# right-angle-extender.net
KiCad netlist of a schematic drawn in EAGLE
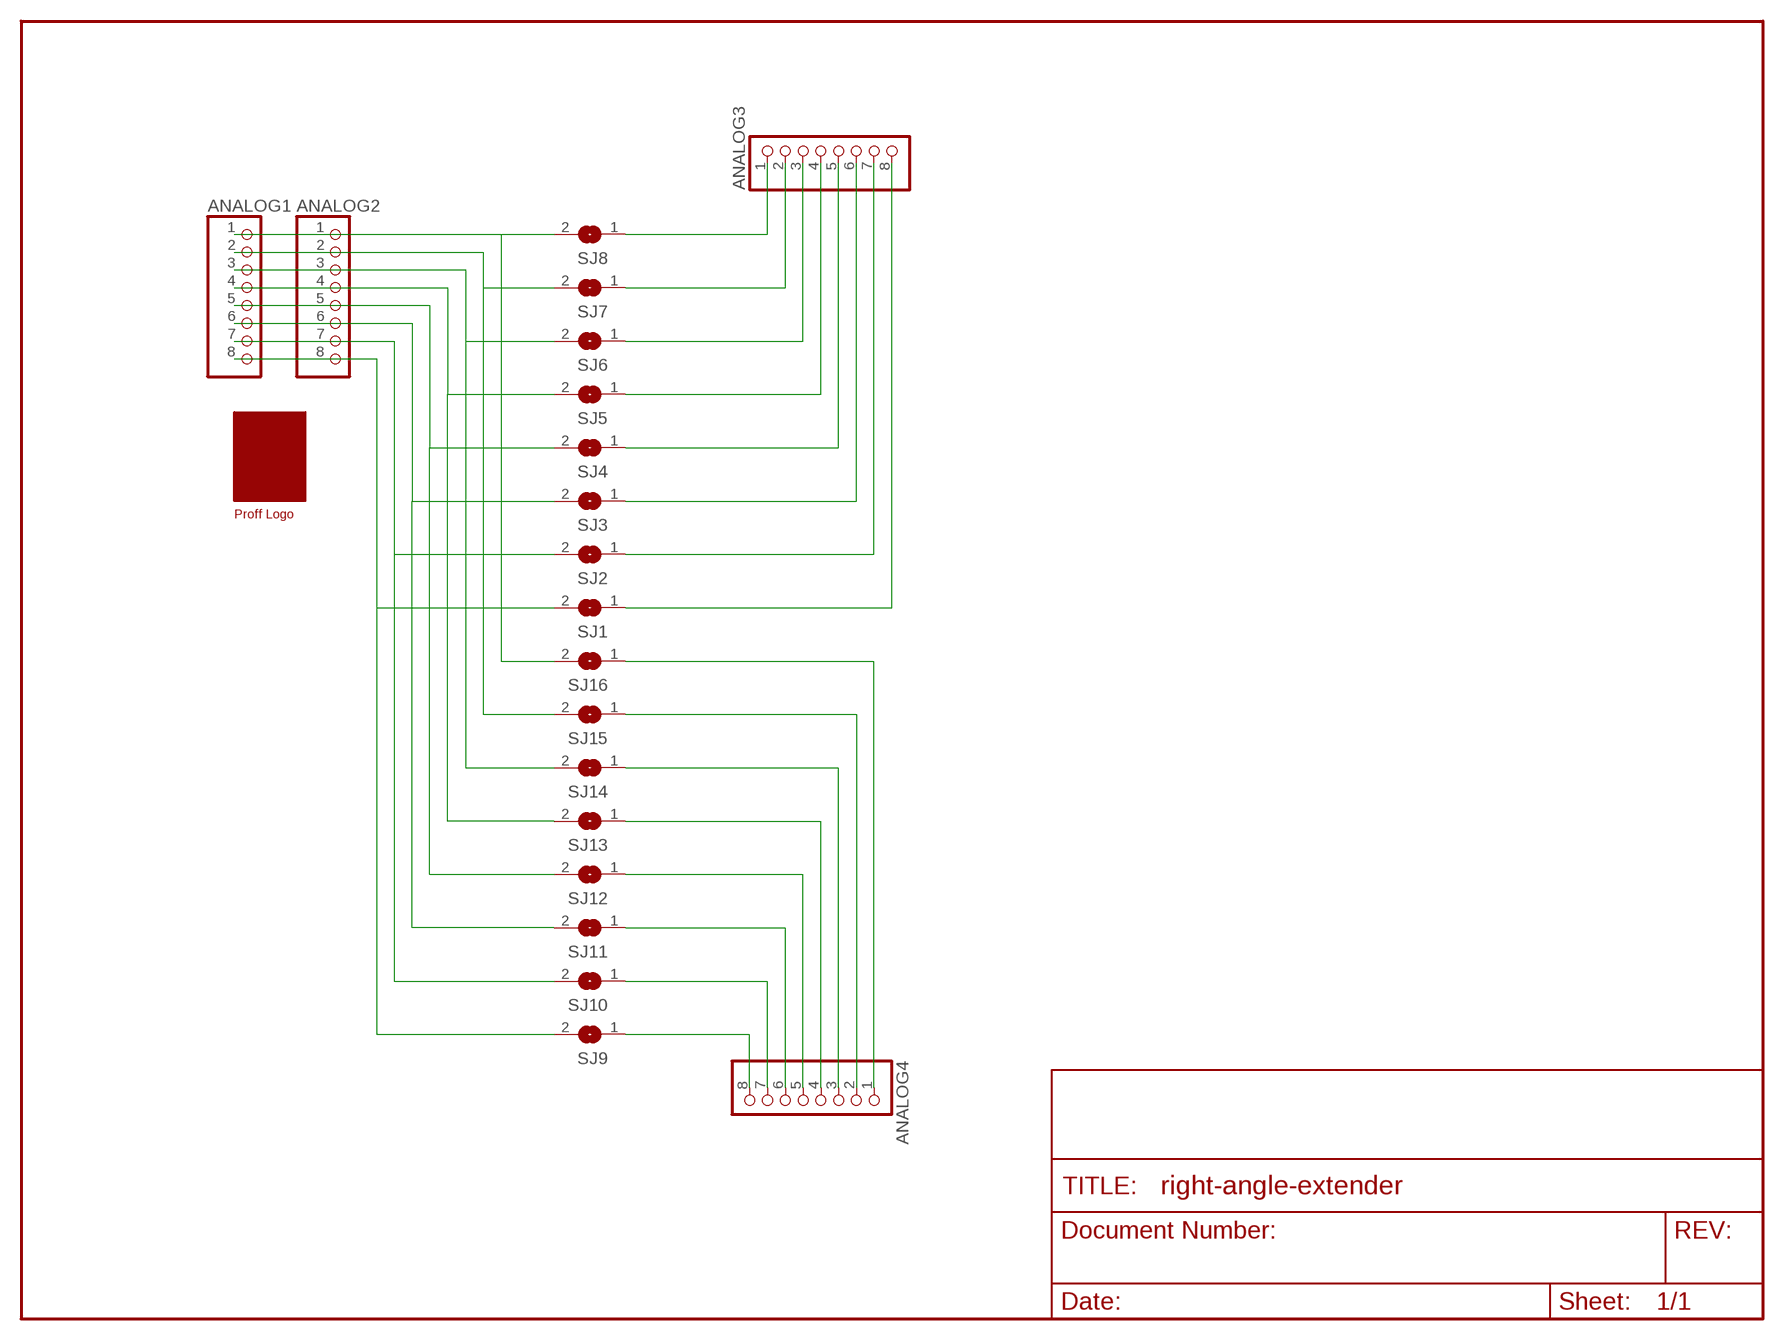
[diagram p0: schematic, sheet 1]

(export (version "E")
  (design (tool "Eeschema 10.0.6"))
  (components
    (comp (ref "ANALOG1")
      (value "PINHD-1X8")
      (footprint "eagle-import:1X08")
      (libsource (lib "eagle-import") (part "PINHD-1X8"))
    )
    (comp (ref "ANALOG2")
      (value "PINHD-1X8")
      (footprint "eagle-import:1X08")
      (libsource (lib "eagle-import") (part "PINHD-1X8"))
    )
    (comp (ref "ANALOG3")
      (value "PINHD-1X8")
      (footprint "eagle-import:1X08")
      (libsource (lib "eagle-import") (part "PINHD-1X8"))
    )
    (comp (ref "ANALOG4")
      (value "PINHD-1X8")
      (footprint "eagle-import:1X08")
      (libsource (lib "eagle-import") (part "PINHD-1X8"))
    )
    (comp (ref "SJ1") (value "SJ") (footprint "eagle-import:SJ") (libsource (lib "eagle-import") (part "SJ")))
    (comp (ref "SJ2") (value "SJ") (footprint "eagle-import:SJ") (libsource (lib "eagle-import") (part "SJ")))
    (comp (ref "SJ3") (value "SJ") (footprint "eagle-import:SJ") (libsource (lib "eagle-import") (part "SJ")))
    (comp (ref "SJ4") (value "SJ") (footprint "eagle-import:SJ") (libsource (lib "eagle-import") (part "SJ")))
    (comp (ref "SJ5") (value "SJ") (footprint "eagle-import:SJ") (libsource (lib "eagle-import") (part "SJ")))
    (comp (ref "SJ6") (value "SJ") (footprint "eagle-import:SJ") (libsource (lib "eagle-import") (part "SJ")))
    (comp (ref "SJ7") (value "SJ") (footprint "eagle-import:SJ") (libsource (lib "eagle-import") (part "SJ")))
    (comp (ref "SJ8") (value "SJ") (footprint "eagle-import:SJ") (libsource (lib "eagle-import") (part "SJ")))
    (comp (ref "SJ9") (value "SJ") (footprint "eagle-import:SJ") (libsource (lib "eagle-import") (part "SJ")))
    (comp (ref "SJ10")
      (value "SJ")
      (footprint "eagle-import:SJ")
      (libsource (lib "eagle-import") (part "SJ"))
    )
    (comp (ref "SJ11")
      (value "SJ")
      (footprint "eagle-import:SJ")
      (libsource (lib "eagle-import") (part "SJ"))
    )
    (comp (ref "SJ12")
      (value "SJ")
      (footprint "eagle-import:SJ")
      (libsource (lib "eagle-import") (part "SJ"))
    )
    (comp (ref "SJ13")
      (value "SJ")
      (footprint "eagle-import:SJ")
      (libsource (lib "eagle-import") (part "SJ"))
    )
    (comp (ref "SJ14")
      (value "SJ")
      (footprint "eagle-import:SJ")
      (libsource (lib "eagle-import") (part "SJ"))
    )
    (comp (ref "SJ15")
      (value "SJ")
      (footprint "eagle-import:SJ")
      (libsource (lib "eagle-import") (part "SJ"))
    )
    (comp (ref "SJ16")
      (value "SJ")
      (footprint "eagle-import:SJ")
      (libsource (lib "eagle-import") (part "SJ"))
    )
    (comp (ref "U$1")
      (value "PROFF")
      (footprint "eagle-import:PROFF")
      (libsource (lib "eagle-import") (part "PROFF"))
    )
  )
  (nets
    (net (code "1") (name "Net-(ANALOG1-Pad1)") (class "Default")
      (node (ref "ANALOG1") (pin "1") (pinfunction "1_1") (pintype "passive"))
      (node (ref "ANALOG2") (pin "1") (pinfunction "1_1") (pintype "passive"))
      (node (ref "SJ16") (pin "2") (pinfunction "2_2") (pintype "passive"))
      (node (ref "SJ8") (pin "2") (pinfunction "2_2") (pintype "passive"))
    )
    (net (code "2") (name "Net-(ANALOG1-Pad2)") (class "Default")
      (node (ref "ANALOG1") (pin "2") (pinfunction "2_2") (pintype "passive"))
      (node (ref "ANALOG2") (pin "2") (pinfunction "2_2") (pintype "passive"))
      (node (ref "SJ15") (pin "2") (pinfunction "2_2") (pintype "passive"))
      (node (ref "SJ7") (pin "2") (pinfunction "2_2") (pintype "passive"))
    )
    (net (code "3") (name "Net-(ANALOG1-Pad3)") (class "Default")
      (node (ref "ANALOG1") (pin "3") (pinfunction "3_3") (pintype "passive"))
      (node (ref "ANALOG2") (pin "3") (pinfunction "3_3") (pintype "passive"))
      (node (ref "SJ14") (pin "2") (pinfunction "2_2") (pintype "passive"))
      (node (ref "SJ6") (pin "2") (pinfunction "2_2") (pintype "passive"))
    )
    (net (code "4") (name "Net-(ANALOG1-Pad4)") (class "Default")
      (node (ref "ANALOG1") (pin "4") (pinfunction "4_4") (pintype "passive"))
      (node (ref "ANALOG2") (pin "4") (pinfunction "4_4") (pintype "passive"))
      (node (ref "SJ13") (pin "2") (pinfunction "2_2") (pintype "passive"))
      (node (ref "SJ5") (pin "2") (pinfunction "2_2") (pintype "passive"))
    )
    (net (code "5") (name "Net-(ANALOG1-Pad5)") (class "Default")
      (node (ref "ANALOG1") (pin "5") (pinfunction "5_5") (pintype "passive"))
      (node (ref "ANALOG2") (pin "5") (pinfunction "5_5") (pintype "passive"))
      (node (ref "SJ12") (pin "2") (pinfunction "2_2") (pintype "passive"))
      (node (ref "SJ4") (pin "2") (pinfunction "2_2") (pintype "passive"))
    )
    (net (code "6") (name "Net-(ANALOG1-Pad6)") (class "Default")
      (node (ref "ANALOG1") (pin "6") (pinfunction "6_6") (pintype "passive"))
      (node (ref "ANALOG2") (pin "6") (pinfunction "6_6") (pintype "passive"))
      (node (ref "SJ11") (pin "2") (pinfunction "2_2") (pintype "passive"))
      (node (ref "SJ3") (pin "2") (pinfunction "2_2") (pintype "passive"))
    )
    (net (code "7") (name "Net-(ANALOG1-Pad7)") (class "Default")
      (node (ref "ANALOG1") (pin "7") (pinfunction "7_7") (pintype "passive"))
      (node (ref "ANALOG2") (pin "7") (pinfunction "7_7") (pintype "passive"))
      (node (ref "SJ10") (pin "2") (pinfunction "2_2") (pintype "passive"))
      (node (ref "SJ2") (pin "2") (pinfunction "2_2") (pintype "passive"))
    )
    (net (code "8") (name "Net-(ANALOG1-Pad8)") (class "Default")
      (node (ref "ANALOG1") (pin "8") (pinfunction "8_8") (pintype "passive"))
      (node (ref "ANALOG2") (pin "8") (pinfunction "8_8") (pintype "passive"))
      (node (ref "SJ1") (pin "2") (pinfunction "2_2") (pintype "passive"))
      (node (ref "SJ9") (pin "2") (pinfunction "2_2") (pintype "passive"))
    )
    (net (code "9") (name "Net-(ANALOG3-Pad1)") (class "Default")
      (node (ref "ANALOG3") (pin "1") (pinfunction "1_1") (pintype "passive"))
      (node (ref "SJ8") (pin "1") (pinfunction "1_1") (pintype "passive"))
    )
    (net (code "10") (name "Net-(ANALOG3-Pad2)") (class "Default")
      (node (ref "ANALOG3") (pin "2") (pinfunction "2_2") (pintype "passive"))
      (node (ref "SJ7") (pin "1") (pinfunction "1_1") (pintype "passive"))
    )
    (net (code "11") (name "Net-(ANALOG3-Pad3)") (class "Default")
      (node (ref "ANALOG3") (pin "3") (pinfunction "3_3") (pintype "passive"))
      (node (ref "SJ6") (pin "1") (pinfunction "1_1") (pintype "passive"))
    )
    (net (code "12") (name "Net-(ANALOG3-Pad4)") (class "Default")
      (node (ref "ANALOG3") (pin "4") (pinfunction "4_4") (pintype "passive"))
      (node (ref "SJ5") (pin "1") (pinfunction "1_1") (pintype "passive"))
    )
    (net (code "13") (name "Net-(ANALOG3-Pad5)") (class "Default")
      (node (ref "ANALOG3") (pin "5") (pinfunction "5_5") (pintype "passive"))
      (node (ref "SJ4") (pin "1") (pinfunction "1_1") (pintype "passive"))
    )
    (net (code "14") (name "Net-(ANALOG3-Pad6)") (class "Default")
      (node (ref "ANALOG3") (pin "6") (pinfunction "6_6") (pintype "passive"))
      (node (ref "SJ3") (pin "1") (pinfunction "1_1") (pintype "passive"))
    )
    (net (code "15") (name "Net-(ANALOG3-Pad7)") (class "Default")
      (node (ref "ANALOG3") (pin "7") (pinfunction "7_7") (pintype "passive"))
      (node (ref "SJ2") (pin "1") (pinfunction "1_1") (pintype "passive"))
    )
    (net (code "16") (name "Net-(ANALOG3-Pad8)") (class "Default")
      (node (ref "ANALOG3") (pin "8") (pinfunction "8_8") (pintype "passive"))
      (node (ref "SJ1") (pin "1") (pinfunction "1_1") (pintype "passive"))
    )
    (net (code "17") (name "Net-(ANALOG4-Pad1)") (class "Default")
      (node (ref "ANALOG4") (pin "1") (pinfunction "1_1") (pintype "passive"))
      (node (ref "SJ16") (pin "1") (pinfunction "1_1") (pintype "passive"))
    )
    (net (code "18") (name "Net-(ANALOG4-Pad2)") (class "Default")
      (node (ref "ANALOG4") (pin "2") (pinfunction "2_2") (pintype "passive"))
      (node (ref "SJ15") (pin "1") (pinfunction "1_1") (pintype "passive"))
    )
    (net (code "19") (name "Net-(ANALOG4-Pad3)") (class "Default")
      (node (ref "ANALOG4") (pin "3") (pinfunction "3_3") (pintype "passive"))
      (node (ref "SJ14") (pin "1") (pinfunction "1_1") (pintype "passive"))
    )
    (net (code "20") (name "Net-(ANALOG4-Pad4)") (class "Default")
      (node (ref "ANALOG4") (pin "4") (pinfunction "4_4") (pintype "passive"))
      (node (ref "SJ13") (pin "1") (pinfunction "1_1") (pintype "passive"))
    )
    (net (code "21") (name "Net-(ANALOG4-Pad5)") (class "Default")
      (node (ref "ANALOG4") (pin "5") (pinfunction "5_5") (pintype "passive"))
      (node (ref "SJ12") (pin "1") (pinfunction "1_1") (pintype "passive"))
    )
    (net (code "22") (name "Net-(ANALOG4-Pad6)") (class "Default")
      (node (ref "ANALOG4") (pin "6") (pinfunction "6_6") (pintype "passive"))
      (node (ref "SJ11") (pin "1") (pinfunction "1_1") (pintype "passive"))
    )
    (net (code "23") (name "Net-(ANALOG4-Pad7)") (class "Default")
      (node (ref "ANALOG4") (pin "7") (pinfunction "7_7") (pintype "passive"))
      (node (ref "SJ10") (pin "1") (pinfunction "1_1") (pintype "passive"))
    )
    (net (code "24") (name "Net-(ANALOG4-Pad8)") (class "Default")
      (node (ref "ANALOG4") (pin "8") (pinfunction "8_8") (pintype "passive"))
      (node (ref "SJ9") (pin "1") (pinfunction "1_1") (pintype "passive"))
    )
  )
)
